# Sensor_ExpandBoard_MPU6050.net
KiCad netlist of a schematic drawn in Altium Designer
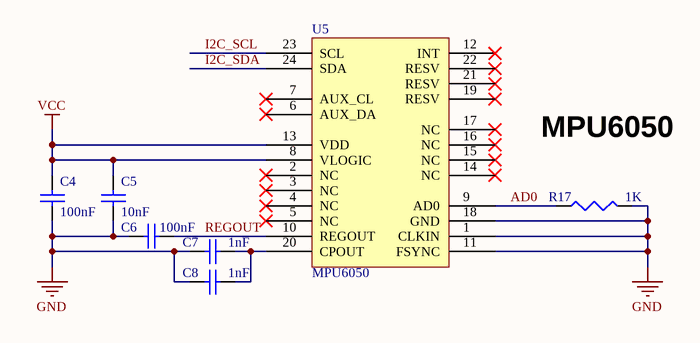
[diagram p0: Sensor_ExpandBoard_MPU6050.SchDoc]

(export (version "E")
  (design (tool "Eeschema 10.0.6"))
  (components
    (comp (ref "C4")
      (value "100nF")
      (footprint "0603-2")
      (description "无极性电容")
      (fields (field (name "PUBLISHER") "Altium Limited"))
      (libsource (lib "Fszhang") (part "Cap"))
    )
    (comp (ref "C5")
      (value "10nF")
      (footprint "0603-2")
      (description "无极性电容")
      (fields (field (name "PUBLISHER") "Altium Limited"))
      (libsource (lib "Fszhang") (part "Cap"))
    )
    (comp (ref "C6")
      (value "100nF")
      (footprint "0603-2")
      (description "无极性电容")
      (fields (field (name "PUBLISHER") "Altium Limited"))
      (libsource (lib "Fszhang") (part "Cap"))
    )
    (comp (ref "C7")
      (value "1nF")
      (footprint "0603-2")
      (description "无极性电容")
      (fields (field (name "PUBLISHER") "Altium Limited"))
      (libsource (lib "Fszhang") (part "Cap"))
    )
    (comp (ref "C8")
      (value "1nF")
      (footprint "0603-2")
      (description "无极性电容")
      (fields (field (name "PUBLISHER") "Altium Limited"))
      (libsource (lib "Fszhang") (part "Cap"))
    )
    (comp (ref "R17")
      (value "1K")
      (footprint "R0603")
      (description "Resistor")
      (fields (field (name "PUBLISHER") "Altium Limited"))
      (libsource (lib "step") (part "Res"))
    )
    (comp (ref "U5")
      (value "MPU6050")
      (footprint "QFN24")
      (description "6轴传感器，QFN24")
      (fields (field (name "PUBLISHER") "Altium Limited"))
      (libsource (lib "Sensor") (part "MPU6050"))
    )
  )
  (nets
    (net (code "1") (name "/AD0") (class "Default")
      (node (ref "R17") (pin "1") (pinfunction "1_1") (pintype "passive"))
      (node (ref "U5") (pin "9") (pinfunction "AD0_9") (pintype "passive"))
    )
    (net (code "2") (name "/I2C_SCL") (class "Default")
      (node (ref "U5") (pin "23") (pinfunction "SCL_23") (pintype "passive"))
    )
    (net (code "3") (name "/I2C_SDA") (class "Default")
      (node (ref "U5") (pin "24") (pinfunction "SDA_24") (pintype "passive"))
    )
    (net (code "4") (name "/REGOUT") (class "Default")
      (node (ref "C6") (pin "1") (pinfunction "1_1") (pintype "passive"))
      (node (ref "U5") (pin "10") (pinfunction "REGOUT_10") (pintype "passive"))
    )
    (net (code "5") (name "GND") (class "Default")
      (node (ref "C4") (pin "2") (pinfunction "2_2") (pintype "passive"))
      (node (ref "C5") (pin "2") (pinfunction "2_2") (pintype "passive"))
      (node (ref "C6") (pin "2") (pinfunction "2_2") (pintype "passive"))
      (node (ref "C7") (pin "2") (pinfunction "2_2") (pintype "passive"))
      (node (ref "C8") (pin "1") (pinfunction "1_1") (pintype "passive"))
      (node (ref "R17") (pin "2") (pinfunction "2_2") (pintype "passive"))
      (node (ref "U5") (pin "1") (pinfunction "CLKIN_1") (pintype "passive"))
      (node (ref "U5") (pin "11") (pinfunction "FSYNC_11") (pintype "passive"))
      (node (ref "U5") (pin "18") (pinfunction "GND_18") (pintype "passive"))
    )
    (net (code "6") (name "Net-(U5-CPOUT)") (class "Default")
      (node (ref "C7") (pin "1") (pinfunction "1_1") (pintype "passive"))
      (node (ref "C8") (pin "2") (pinfunction "2_2") (pintype "passive"))
      (node (ref "U5") (pin "20") (pinfunction "CPOUT_20") (pintype "passive"))
    )
    (net (code "7") (name "VCC") (class "Default")
      (node (ref "C4") (pin "1") (pinfunction "1_1") (pintype "passive"))
      (node (ref "C5") (pin "1") (pinfunction "1_1") (pintype "passive"))
      (node (ref "U5") (pin "13") (pinfunction "VDD_13") (pintype "passive"))
      (node (ref "U5") (pin "8") (pinfunction "VLOGIC_8") (pintype "passive"))
    )
    (net (code "8") (name "unconnected-(U5-AUX_CL-Pad7)") (class "Default")
      (node (ref "U5") (pin "7") (pinfunction "AUX_CL_7") (pintype "passive+no_connect"))
    )
    (net (code "9") (name "unconnected-(U5-AUX_DA-Pad6)") (class "Default")
      (node (ref "U5") (pin "6") (pinfunction "AUX_DA_6") (pintype "passive+no_connect"))
    )
    (net (code "10") (name "unconnected-(U5-INT-Pad12)") (class "Default")
      (node (ref "U5") (pin "12") (pinfunction "INT_12") (pintype "passive+no_connect"))
    )
    (net (code "11") (name "unconnected-(U5-NC-Pad2)") (class "Default")
      (node (ref "U5") (pin "2") (pinfunction "NC_2") (pintype "passive+no_connect"))
    )
    (net (code "12") (name "unconnected-(U5-NC-Pad3)") (class "Default")
      (node (ref "U5") (pin "3") (pinfunction "NC_3") (pintype "passive+no_connect"))
    )
    (net (code "13") (name "unconnected-(U5-NC-Pad4)") (class "Default")
      (node (ref "U5") (pin "4") (pinfunction "NC_4") (pintype "passive+no_connect"))
    )
    (net (code "14") (name "unconnected-(U5-NC-Pad5)") (class "Default")
      (node (ref "U5") (pin "5") (pinfunction "NC_5") (pintype "passive+no_connect"))
    )
    (net (code "15") (name "unconnected-(U5-NC-Pad14)") (class "Default")
      (node (ref "U5") (pin "14") (pinfunction "NC_14") (pintype "passive+no_connect"))
    )
    (net (code "16") (name "unconnected-(U5-NC-Pad15)") (class "Default")
      (node (ref "U5") (pin "15") (pinfunction "NC_15") (pintype "passive+no_connect"))
    )
    (net (code "17") (name "unconnected-(U5-NC-Pad16)") (class "Default")
      (node (ref "U5") (pin "16") (pinfunction "NC_16") (pintype "passive+no_connect"))
    )
    (net (code "18") (name "unconnected-(U5-NC-Pad17)") (class "Default")
      (node (ref "U5") (pin "17") (pinfunction "NC_17") (pintype "passive+no_connect"))
    )
    (net (code "19") (name "unconnected-(U5-RESV-Pad19)") (class "Default")
      (node (ref "U5") (pin "19") (pinfunction "RESV_19") (pintype "passive+no_connect"))
    )
    (net (code "20") (name "unconnected-(U5-RESV-Pad21)") (class "Default")
      (node (ref "U5") (pin "21") (pinfunction "RESV_21") (pintype "passive+no_connect"))
    )
    (net (code "21") (name "unconnected-(U5-RESV-Pad22)") (class "Default")
      (node (ref "U5") (pin "22") (pinfunction "RESV_22") (pintype "passive+no_connect"))
    )
  )
)
